# AS5048_Encoder.net
KiCad netlist of a schematic drawn in EAGLE
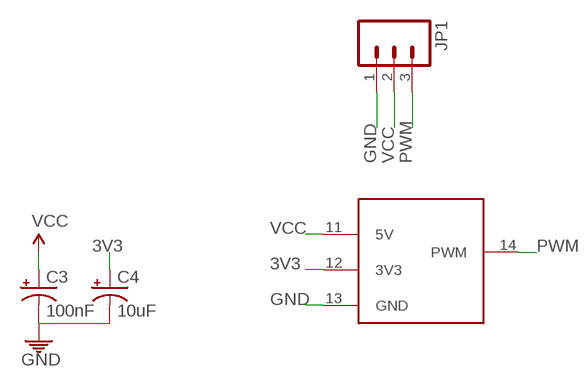
[diagram p0: schematic, sheet 1]

(export (version "E")
  (design (tool "Eeschema 10.0.6"))
  (components
    (comp (ref "C3")
      (value "100nF")
      (footprint "eagle-import:EIA3216-KIT")
      (libsource (lib "eagle-import") (part "CAP_POL1206-KIT"))
    )
    (comp (ref "C4")
      (value "10uF")
      (footprint "eagle-import:EIA3216-KIT")
      (libsource (lib "eagle-import") (part "CAP_POL1206-KIT"))
    )
    (comp (ref "JP1")
      (value "M03LOCK")
      (footprint "eagle-import:1X03_LOCK")
      (libsource (lib "eagle-import") (part "M03LOCK"))
    )
    (comp (ref "U$1")
      (value "AS5048")
      (footprint "eagle-import:TSOP14")
      (libsource (lib "eagle-import") (part "AS5048"))
    )
  )
  (nets
    (net (code "1") (name "/3V3") (class "Default")
      (node (ref "C4") (pin "A") (pinfunction "+_A") (pintype "passive"))
      (node (ref "U$1") (pin "12") (pinfunction "3V3_12") (pintype "bidirectional"))
    )
    (net (code "2") (name "/PWM") (class "Default")
      (node (ref "JP1") (pin "3") (pinfunction "3_3") (pintype "passive"))
      (node (ref "U$1") (pin "14") (pinfunction "PWM_14") (pintype "bidirectional"))
    )
    (net (code "3") (name "GND") (class "Default")
      (node (ref "C3") (pin "C") (pinfunction "-_C") (pintype "passive"))
      (node (ref "C4") (pin "C") (pinfunction "-_C") (pintype "passive"))
      (node (ref "JP1") (pin "1") (pinfunction "1_1") (pintype "passive"))
      (node (ref "U$1") (pin "13") (pinfunction "GND_13") (pintype "bidirectional"))
    )
    (net (code "4") (name "VCC") (class "Default")
      (node (ref "C3") (pin "A") (pinfunction "+_A") (pintype "passive"))
      (node (ref "JP1") (pin "2") (pinfunction "2_2") (pintype "passive"))
      (node (ref "U$1") (pin "11") (pinfunction "5V_11") (pintype "bidirectional"))
    )
  )
)
